# Sheet3.net
KiCad netlist of a schematic drawn in Altium Designer
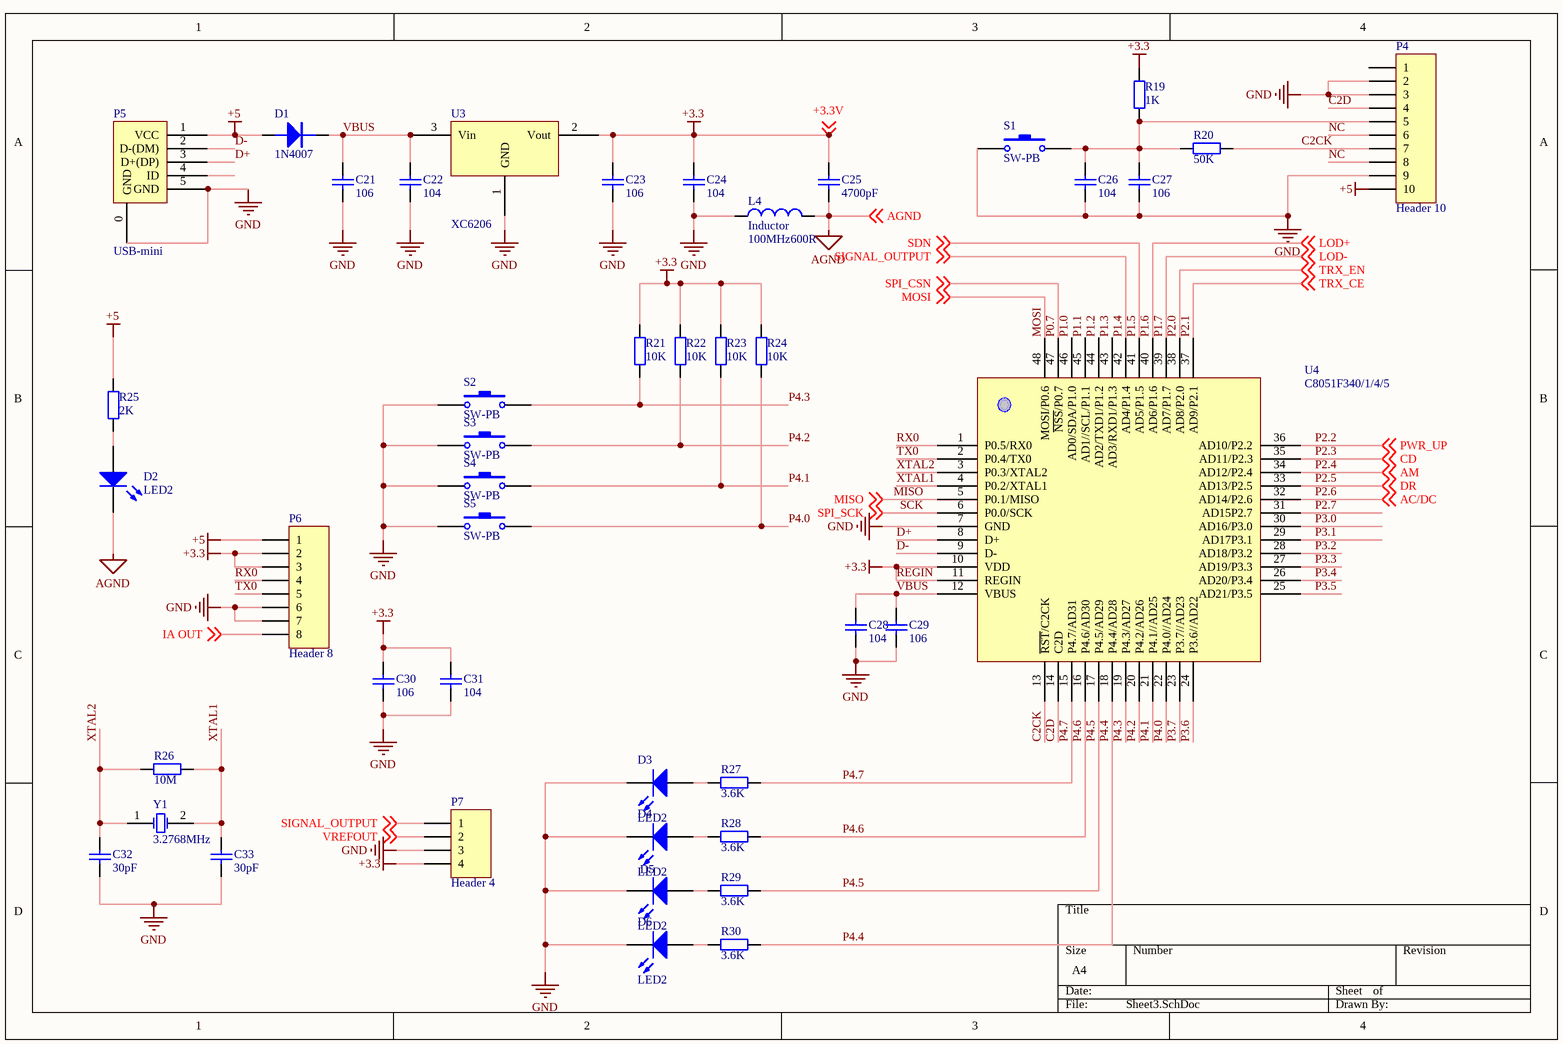
[diagram p0: Sheet3.SchDoc]

(export (version "E")
  (design (tool "Eeschema 10.0.6"))
  (components
    (comp (ref "C21")
      (value "106")
      (footprint "0603C")
      (description "Capacitor")
      (fields (field (name "PUBLISHER") "Altium Limited"))
      (libsource (lib "ECG.SCHLIB") (part "Cap"))
    )
    (comp (ref "C22")
      (value "104")
      (footprint "0603C")
      (description "Capacitor")
      (fields (field (name "PUBLISHER") "Altium Limited"))
      (libsource (lib "ECG.SCHLIB") (part "Cap"))
    )
    (comp (ref "C23")
      (value "106")
      (footprint "0603C")
      (description "Capacitor")
      (fields (field (name "PUBLISHER") "Altium Limited"))
      (libsource (lib "ECG.SCHLIB") (part "Cap"))
    )
    (comp (ref "C24")
      (value "104")
      (footprint "0603C")
      (description "Capacitor")
      (fields (field (name "PUBLISHER") "Altium Limited"))
      (libsource (lib "ECG.SCHLIB") (part "Cap"))
    )
    (comp (ref "C25")
      (value "4700pF")
      (footprint "0603C")
      (description "Capacitor")
      (fields (field (name "PUBLISHER") "Altium Limited"))
      (libsource (lib "ECG.SCHLIB") (part "Cap"))
    )
    (comp (ref "C26")
      (value "104")
      (footprint "0603C")
      (description "Capacitor")
      (fields (field (name "PUBLISHER") "Altium Limited"))
      (libsource (lib "ECG.SCHLIB") (part "Cap"))
    )
    (comp (ref "C27")
      (value "106")
      (footprint "0603C")
      (description "Capacitor")
      (fields (field (name "PUBLISHER") "Altium Limited"))
      (libsource (lib "ECG.SCHLIB") (part "Cap"))
    )
    (comp (ref "C28")
      (value "104")
      (footprint "0603C")
      (description "Capacitor")
      (fields (field (name "PUBLISHER") "Altium Limited"))
      (libsource (lib "ECG.SCHLIB") (part "Cap"))
    )
    (comp (ref "C29")
      (value "106")
      (footprint "0603C")
      (description "Capacitor")
      (fields (field (name "PUBLISHER") "Altium Limited"))
      (libsource (lib "ECG.SCHLIB") (part "Cap"))
    )
    (comp (ref "C30")
      (value "106")
      (footprint "0603C")
      (description "Capacitor")
      (fields (field (name "PUBLISHER") "Altium Limited"))
      (libsource (lib "ECG.SCHLIB") (part "Cap"))
    )
    (comp (ref "C31")
      (value "104")
      (footprint "0603C")
      (description "Capacitor")
      (fields (field (name "PUBLISHER") "Altium Limited"))
      (libsource (lib "ECG.SCHLIB") (part "Cap"))
    )
    (comp (ref "C32")
      (value "30pF")
      (footprint "0603C")
      (description "Capacitor")
      (fields (field (name "PUBLISHER") "Altium Limited"))
      (libsource (lib "ECG.SCHLIB") (part "Cap"))
    )
    (comp (ref "C33")
      (value "30pF")
      (footprint "0603C")
      (description "Capacitor")
      (fields (field (name "PUBLISHER") "Altium Limited"))
      (libsource (lib "ECG.SCHLIB") (part "Cap"))
    )
    (comp (ref "D1") (value "1N4007") (footprint "0603-D") (libsource (lib "ECG2.0") (part "DIODE")))
    (comp (ref "D2")
      (value "LED2")
      (footprint "0603-D")
      (description "Typical RED, GREEN, YELLOW, AMBER GaAs LED")
      (fields (field (name "PUBLISHER") "Altium Limited"))
      (libsource (lib "") (part "LED2_1"))
    )
    (comp (ref "D3")
      (value "LED2")
      (footprint "LED0805R")
      (description "Typical RED, GREEN, YELLOW, AMBER GaAs LED")
      (fields (field (name "PUBLISHER") "Altium Limited"))
      (libsource (lib "Miscellaneous Devices") (part "LED2"))
    )
    (comp (ref "D4")
      (value "LED2")
      (footprint "LED0805R")
      (description "Typical RED, GREEN, YELLOW, AMBER GaAs LED")
      (fields (field (name "PUBLISHER") "Altium Limited"))
      (libsource (lib "Miscellaneous Devices") (part "LED2"))
    )
    (comp (ref "D5")
      (value "LED2")
      (footprint "LED0805R")
      (description "Typical RED, GREEN, YELLOW, AMBER GaAs LED")
      (fields (field (name "PUBLISHER") "Altium Limited"))
      (libsource (lib "Miscellaneous Devices") (part "LED2"))
    )
    (comp (ref "D6")
      (value "LED2")
      (footprint "LED0805R")
      (description "Typical RED, GREEN, YELLOW, AMBER GaAs LED")
      (fields (field (name "PUBLISHER") "Altium Limited"))
      (libsource (lib "Miscellaneous Devices") (part "LED2"))
    )
    (comp (ref "L4")
      (value "Inductor")
      (footprint "0603")
      (fields (field (name "ALTIUM_VALUE") "100MHz600R") (field (name "PUBLISHER") "Altium Limited"))
      (libsource (lib "Miscellaneous Devices") (part "Inductor"))
    )
    (comp (ref "P4")
      (value "Header 10")
      (footprint "IDC10L")
      (description "Header, 10-Pin")
      (fields (field (name "PUBLISHER") "Altium Limited"))
      (libsource (lib "Miscellaneous Connectors") (part "Header 10"))
    )
    (comp (ref "P5") (value "USB-mini") (footprint "USB-Micro") (libsource (lib "ECG2.0") (part "USB-mini")))
    (comp (ref "P6")
      (value "Header 8")
      (footprint "HDR1X8")
      (description "Header, 8-Pin")
      (fields (field (name "PUBLISHER") "Altium Limited"))
      (libsource (lib "Miscellaneous Connectors") (part "Header 8"))
    )
    (comp (ref "P7")
      (value "Header 4")
      (footprint "HDR1X4")
      (description "Header, 4-Pin")
      (fields (field (name "PUBLISHER") "Altium Limited"))
      (libsource (lib "Miscellaneous Connectors") (part "Header 4"))
    )
    (comp (ref "R19")
      (value "1K")
      (footprint "0603R")
      (description "Resistor")
      (fields (field (name "PUBLISHER") "Altium Limited"))
      (libsource (lib "") (part "Res2_2"))
    )
    (comp (ref "R20")
      (value "50K")
      (footprint "0603R")
      (description "Resistor")
      (fields (field (name "PUBLISHER") "Altium Limited"))
      (libsource (lib "") (part "Res2_1"))
    )
    (comp (ref "R21")
      (value "10K")
      (footprint "0603R")
      (description "Resistor")
      (fields (field (name "PUBLISHER") "Altium Limited"))
      (libsource (lib "") (part "Res2_2"))
    )
    (comp (ref "R22")
      (value "10K")
      (footprint "0603R")
      (description "Resistor")
      (fields (field (name "PUBLISHER") "Altium Limited"))
      (libsource (lib "") (part "Res2_2"))
    )
    (comp (ref "R23")
      (value "10K")
      (footprint "0603R")
      (description "Resistor")
      (fields (field (name "PUBLISHER") "Altium Limited"))
      (libsource (lib "") (part "Res2_2"))
    )
    (comp (ref "R24")
      (value "10K")
      (footprint "0603R")
      (description "Resistor")
      (fields (field (name "PUBLISHER") "Altium Limited"))
      (libsource (lib "") (part "Res2_2"))
    )
    (comp (ref "R25")
      (value "2K")
      (footprint "0603R")
      (description "Resistor")
      (fields (field (name "PUBLISHER") "Altium Limited"))
      (libsource (lib "") (part "Res2_2"))
    )
    (comp (ref "R26")
      (value "10M")
      (footprint "0603R")
      (description "Resistor")
      (fields (field (name "PUBLISHER") "Altium Limited"))
      (libsource (lib "ECG.SCHLIB") (part "Res2"))
    )
    (comp (ref "R27")
      (value "3.6K")
      (footprint "0603R")
      (description "Resistor")
      (fields (field (name "PUBLISHER") "Altium Limited"))
      (libsource (lib "ECG.SCHLIB") (part "Res2"))
    )
    (comp (ref "R28")
      (value "3.6K")
      (footprint "0603R")
      (description "Resistor")
      (fields (field (name "PUBLISHER") "Altium Limited"))
      (libsource (lib "ECG.SCHLIB") (part "Res2"))
    )
    (comp (ref "R29")
      (value "3.6K")
      (footprint "0603R")
      (description "Resistor")
      (fields (field (name "PUBLISHER") "Altium Limited"))
      (libsource (lib "ECG.SCHLIB") (part "Res2"))
    )
    (comp (ref "R30")
      (value "3.6K")
      (footprint "0603R")
      (description "Resistor")
      (fields (field (name "PUBLISHER") "Altium Limited"))
      (libsource (lib "ECG.SCHLIB") (part "Res2"))
    )
    (comp (ref "S1")
      (value "SW-PB")
      (footprint "SW-BP-SMD")
      (description "Switch")
      (fields (field (name "PUBLISHER") "Altium Limited"))
      (libsource (lib "Miscellaneous Devices") (part "SW-PB"))
    )
    (comp (ref "S2")
      (value "SW-PB")
      (footprint "SW-BP-SMD")
      (description "Switch")
      (fields (field (name "PUBLISHER") "Altium Limited"))
      (libsource (lib "Miscellaneous Devices") (part "SW-PB"))
    )
    (comp (ref "S3")
      (value "SW-PB")
      (footprint "SW-BP-SMD")
      (description "Switch")
      (fields (field (name "PUBLISHER") "Altium Limited"))
      (libsource (lib "Miscellaneous Devices") (part "SW-PB"))
    )
    (comp (ref "S4")
      (value "SW-PB")
      (footprint "SW-BP-SMD")
      (description "Switch")
      (fields (field (name "PUBLISHER") "Altium Limited"))
      (libsource (lib "Miscellaneous Devices") (part "SW-PB"))
    )
    (comp (ref "S5")
      (value "SW-PB")
      (footprint "SW-BP-SMD")
      (description "Switch")
      (fields (field (name "PUBLISHER") "Altium Limited"))
      (libsource (lib "Miscellaneous Devices") (part "SW-PB"))
    )
    (comp (ref "U3") (value "XC6206") (footprint "SOT-23-123") (libsource (lib "ECG2.0") (part "XC6206")))
    (comp (ref "U4")
      (value "C8051F340/1/4/5")
      (footprint "TQFP48_M")
      (libsource (lib "ECG2.0") (part "C8051F340/1/4/5"))
    )
    (comp (ref "Y1")
      (value "3.2768MHz")
      (footprint "CY2")
      (description "Crystal Oscillator")
      (fields (field (name "PUBLISHER") "Altium Limited"))
      (libsource (lib "Miscellaneous Devices") (part "XTAL"))
    )
  )
  (nets
    (net (code "1") (name "+3.3") (class "Default")
      (node (ref "C23") (pin "2") (pinfunction "2_2") (pintype "passive"))
      (node (ref "C24") (pin "2") (pinfunction "2_2") (pintype "passive"))
      (node (ref "C25") (pin "2") (pinfunction "2_2") (pintype "passive"))
      (node (ref "C30") (pin "2") (pinfunction "2_2") (pintype "passive"))
      (node (ref "C31") (pin "2") (pinfunction "2_2") (pintype "passive"))
      (node (ref "P6") (pin "2") (pinfunction "2_2") (pintype "passive"))
      (node (ref "P6") (pin "3") (pinfunction "3_3") (pintype "passive"))
      (node (ref "P7") (pin "4") (pinfunction "4_4") (pintype "passive"))
      (node (ref "R19") (pin "2") (pinfunction "2_2") (pintype "passive"))
      (node (ref "R21") (pin "2") (pinfunction "2_2") (pintype "passive"))
      (node (ref "R22") (pin "2") (pinfunction "2_2") (pintype "passive"))
      (node (ref "R23") (pin "2") (pinfunction "2_2") (pintype "passive"))
      (node (ref "R24") (pin "2") (pinfunction "2_2") (pintype "passive"))
      (node (ref "U3") (pin "2") (pinfunction "Vout_2") (pintype "passive"))
      (node (ref "U4") (pin "10") (pinfunction "VDD_10") (pintype "passive"))
      (node (ref "U4") (pin "11") (pinfunction "REGIN_11") (pintype "passive"))
    )
    (net (code "2") (name "+5") (class "Default")
      (node (ref "D1") (pin "A") (pintype "passive"))
      (node (ref "P4") (pin "10") (pinfunction "10_10") (pintype "passive"))
      (node (ref "P5") (pin "1") (pinfunction "VCC_1") (pintype "passive"))
      (node (ref "P6") (pin "1") (pinfunction "1_1") (pintype "passive"))
      (node (ref "R25") (pin "2") (pinfunction "2_2") (pintype "passive"))
    )
    (net (code "3") (name "/C2CK") (class "Default")
      (node (ref "P4") (pin "7") (pinfunction "7_7") (pintype "passive"))
      (node (ref "R20") (pin "1") (pinfunction "1_1") (pintype "passive"))
      (node (ref "U4") (pin "13") (pinfunction "~{RST}/C2CK_13") (pintype "passive"))
    )
    (net (code "4") (name "/C2D") (class "Default")
      (node (ref "P4") (pin "4") (pinfunction "4_4") (pintype "passive"))
      (node (ref "U4") (pin "14") (pinfunction "C2D_14") (pintype "passive"))
    )
    (net (code "5") (name "/D+") (class "Default")
      (node (ref "P5") (pin "3") (pinfunction "D+(DP)_3") (pintype "passive"))
      (node (ref "U4") (pin "8") (pinfunction "D+_8") (pintype "passive"))
    )
    (net (code "6") (name "/D-") (class "Default")
      (node (ref "P5") (pin "2") (pinfunction "D-(DM)_2") (pintype "passive"))
      (node (ref "U4") (pin "9") (pinfunction "D-_9") (pintype "passive"))
    )
    (net (code "7") (name "/NC") (class "Default")
      (node (ref "P4") (pin "6") (pinfunction "6_6") (pintype "passive"))
      (node (ref "P4") (pin "8") (pinfunction "8_8") (pintype "passive"))
    )
    (net (code "8") (name "/P1.0") (class "Default")
      (node (ref "U4") (pin "46") (pinfunction "AD0/SDA/P1.0_46") (pintype "passive"))
    )
    (net (code "9") (name "/P1.1") (class "Default")
      (node (ref "U4") (pin "45") (pinfunction "AD1//SCL/P1.1_45") (pintype "passive"))
    )
    (net (code "10") (name "/P1.2") (class "Default")
      (node (ref "U4") (pin "44") (pinfunction "AD2/TXD1/P1.2_44") (pintype "passive"))
    )
    (net (code "11") (name "/P1.3") (class "Default")
      (node (ref "U4") (pin "43") (pinfunction "AD3/RXD1/P1.3_43") (pintype "passive"))
    )
    (net (code "12") (name "/P2.7") (class "Default")
      (node (ref "U4") (pin "31") (pinfunction "AD15P2.7_31") (pintype "passive"))
    )
    (net (code "13") (name "/P3.0") (class "Default")
      (node (ref "U4") (pin "30") (pinfunction "AD16/P3.0_30") (pintype "passive"))
    )
    (net (code "14") (name "/P3.1") (class "Default")
      (node (ref "U4") (pin "29") (pinfunction "AD17P3.1_29") (pintype "passive"))
    )
    (net (code "15") (name "/P3.2") (class "Default")
      (node (ref "U4") (pin "28") (pinfunction "AD18/P3.2_28") (pintype "passive"))
    )
    (net (code "16") (name "/P3.3") (class "Default")
      (node (ref "U4") (pin "27") (pinfunction "AD19/P3.3_27") (pintype "passive"))
    )
    (net (code "17") (name "/P3.4") (class "Default")
      (node (ref "U4") (pin "26") (pinfunction "AD20/P3.4_26") (pintype "passive"))
    )
    (net (code "18") (name "/P3.5") (class "Default")
      (node (ref "U4") (pin "25") (pinfunction "AD21/P3.5_25") (pintype "passive"))
    )
    (net (code "19") (name "/P3.6") (class "Default")
      (node (ref "U4") (pin "24") (pinfunction "P3.6//AD22_24") (pintype "passive"))
    )
    (net (code "20") (name "/P3.7") (class "Default")
      (node (ref "U4") (pin "23") (pinfunction "P3.7//AD23_23") (pintype "passive"))
    )
    (net (code "21") (name "/P4.0") (class "Default")
      (node (ref "R24") (pin "1") (pinfunction "1_1") (pintype "passive"))
      (node (ref "S5") (pin "2") (pinfunction "2_2") (pintype "passive"))
      (node (ref "U4") (pin "22") (pinfunction "P4.0//AD24_22") (pintype "passive"))
    )
    (net (code "22") (name "/P4.1") (class "Default")
      (node (ref "R23") (pin "1") (pinfunction "1_1") (pintype "passive"))
      (node (ref "S4") (pin "2") (pinfunction "2_2") (pintype "passive"))
      (node (ref "U4") (pin "21") (pinfunction "P4.1//AD25_21") (pintype "passive"))
    )
    (net (code "23") (name "/P4.2") (class "Default")
      (node (ref "R22") (pin "1") (pinfunction "1_1") (pintype "passive"))
      (node (ref "S3") (pin "2") (pinfunction "2_2") (pintype "passive"))
      (node (ref "U4") (pin "20") (pinfunction "P4.2/AD26_20") (pintype "passive"))
    )
    (net (code "24") (name "/P4.3") (class "Default")
      (node (ref "R21") (pin "1") (pinfunction "1_1") (pintype "passive"))
      (node (ref "S2") (pin "2") (pinfunction "2_2") (pintype "passive"))
      (node (ref "U4") (pin "19") (pinfunction "P4.3/AD27_19") (pintype "passive"))
    )
    (net (code "25") (name "/P4.4") (class "Default")
      (node (ref "R30") (pin "2") (pinfunction "2_2") (pintype "passive"))
      (node (ref "U4") (pin "18") (pinfunction "P4.4/AD28_18") (pintype "passive"))
    )
    (net (code "26") (name "/P4.5") (class "Default")
      (node (ref "R29") (pin "2") (pinfunction "2_2") (pintype "passive"))
      (node (ref "U4") (pin "17") (pinfunction "P4.5/AD29_17") (pintype "passive"))
    )
    (net (code "27") (name "/P4.6") (class "Default")
      (node (ref "R28") (pin "2") (pinfunction "2_2") (pintype "passive"))
      (node (ref "U4") (pin "16") (pinfunction "P4.6/AD30_16") (pintype "passive"))
    )
    (net (code "28") (name "/P4.7") (class "Default")
      (node (ref "R27") (pin "2") (pinfunction "2_2") (pintype "passive"))
      (node (ref "U4") (pin "15") (pinfunction "P4.7/AD31_15") (pintype "passive"))
    )
    (net (code "29") (name "/RX0") (class "Default")
      (node (ref "P6") (pin "4") (pinfunction "4_4") (pintype "passive"))
      (node (ref "U4") (pin "1") (pinfunction "P0.5/RX0_1") (pintype "passive"))
    )
    (net (code "30") (name "/TX0") (class "Default")
      (node (ref "P6") (pin "5") (pinfunction "5_5") (pintype "passive"))
      (node (ref "U4") (pin "2") (pinfunction "P0.4/TX0_2") (pintype "passive"))
    )
    (net (code "31") (name "/VBUS") (class "Default")
      (node (ref "C21") (pin "2") (pinfunction "2_2") (pintype "passive"))
      (node (ref "C22") (pin "2") (pinfunction "2_2") (pintype "passive"))
      (node (ref "C28") (pin "2") (pinfunction "2_2") (pintype "passive"))
      (node (ref "C29") (pin "2") (pinfunction "2_2") (pintype "passive"))
      (node (ref "D1") (pin "K") (pintype "passive"))
      (node (ref "U3") (pin "3") (pinfunction "Vin_3") (pintype "passive"))
      (node (ref "U4") (pin "12") (pinfunction "VBUS_12") (pintype "passive"))
    )
    (net (code "32") (name "/XTAL1") (class "Default")
      (node (ref "C33") (pin "2") (pinfunction "2_2") (pintype "passive"))
      (node (ref "R26") (pin "2") (pinfunction "2_2") (pintype "passive"))
      (node (ref "U4") (pin "4") (pinfunction "P0.2/XTAL1_4") (pintype "passive"))
      (node (ref "Y1") (pin "2") (pinfunction "OSC2_2") (pintype "passive"))
    )
    (net (code "33") (name "/XTAL2") (class "Default")
      (node (ref "C32") (pin "2") (pinfunction "2_2") (pintype "passive"))
      (node (ref "R26") (pin "1") (pinfunction "1_1") (pintype "passive"))
      (node (ref "U4") (pin "3") (pinfunction "P0.3/XTAL2_3") (pintype "passive"))
      (node (ref "Y1") (pin "1") (pinfunction "OSC1_1") (pintype "passive"))
    )
    (net (code "34") (name "AC{slash}DC") (class "Default")
      (node (ref "U4") (pin "32") (pinfunction "AD14/P2.6_32") (pintype "passive"))
    )
    (net (code "35") (name "AGND") (class "Default")
      (node (ref "C25") (pin "1") (pinfunction "1_1") (pintype "passive"))
      (node (ref "D2") (pin "K") (pinfunction "2_K") (pintype "passive"))
      (node (ref "L4") (pin "2") (pinfunction "2_2") (pintype "passive"))
    )
    (net (code "36") (name "AM") (class "Default")
      (node (ref "U4") (pin "34") (pinfunction "AD12/P2.4_34") (pintype "passive"))
    )
    (net (code "37") (name "CD") (class "Default")
      (node (ref "U4") (pin "35") (pinfunction "AD11/P2.3_35") (pintype "passive"))
    )
    (net (code "38") (name "DR") (class "Default")
      (node (ref "U4") (pin "33") (pinfunction "AD13/P2.5_33") (pintype "passive"))
    )
    (net (code "39") (name "GND") (class "Default")
      (node (ref "C21") (pin "1") (pinfunction "1_1") (pintype "passive"))
      (node (ref "C22") (pin "1") (pinfunction "1_1") (pintype "passive"))
      (node (ref "C23") (pin "1") (pinfunction "1_1") (pintype "passive"))
      (node (ref "C24") (pin "1") (pinfunction "1_1") (pintype "passive"))
      (node (ref "C26") (pin "1") (pinfunction "1_1") (pintype "passive"))
      (node (ref "C27") (pin "1") (pinfunction "1_1") (pintype "passive"))
      (node (ref "C28") (pin "1") (pinfunction "1_1") (pintype "passive"))
      (node (ref "C29") (pin "1") (pinfunction "1_1") (pintype "passive"))
      (node (ref "C30") (pin "1") (pinfunction "1_1") (pintype "passive"))
      (node (ref "C31") (pin "1") (pinfunction "1_1") (pintype "passive"))
      (node (ref "C32") (pin "1") (pinfunction "1_1") (pintype "passive"))
      (node (ref "C33") (pin "1") (pinfunction "1_1") (pintype "passive"))
      (node (ref "D3") (pin "2") (pinfunction "2_2") (pintype "passive"))
      (node (ref "D4") (pin "2") (pinfunction "2_2") (pintype "passive"))
      (node (ref "D5") (pin "2") (pinfunction "2_2") (pintype "passive"))
      (node (ref "D6") (pin "2") (pinfunction "2_2") (pintype "passive"))
      (node (ref "L4") (pin "1") (pinfunction "1_1") (pintype "passive"))
      (node (ref "P4") (pin "2") (pinfunction "2_2") (pintype "passive"))
      (node (ref "P4") (pin "3") (pinfunction "3_3") (pintype "passive"))
      (node (ref "P4") (pin "9") (pinfunction "9_9") (pintype "passive"))
      (node (ref "P5") (pin "0") (pinfunction "GND_0") (pintype "passive"))
      (node (ref "P5") (pin "5") (pinfunction "GND_5") (pintype "passive"))
      (node (ref "P6") (pin "6") (pinfunction "6_6") (pintype "passive"))
      (node (ref "P6") (pin "7") (pinfunction "7_7") (pintype "passive"))
      (node (ref "P7") (pin "3") (pinfunction "3_3") (pintype "passive"))
      (node (ref "S1") (pin "1") (pinfunction "1_1") (pintype "passive"))
      (node (ref "S2") (pin "1") (pinfunction "1_1") (pintype "passive"))
      (node (ref "S3") (pin "1") (pinfunction "1_1") (pintype "passive"))
      (node (ref "S4") (pin "1") (pinfunction "1_1") (pintype "passive"))
      (node (ref "S5") (pin "1") (pinfunction "1_1") (pintype "passive"))
      (node (ref "U3") (pin "1") (pinfunction "GND_1") (pintype "passive"))
      (node (ref "U4") (pin "7") (pinfunction "GND_7") (pintype "passive"))
    )
    (net (code "40") (name "IA OUT") (class "Default")
      (node (ref "P6") (pin "8") (pinfunction "8_8") (pintype "passive"))
    )
    (net (code "41") (name "LOD+") (class "Default")
      (node (ref "U4") (pin "40") (pinfunction "AD6/P1.6_40") (pintype "passive"))
    )
    (net (code "42") (name "LOD-") (class "Default")
      (node (ref "U4") (pin "39") (pinfunction "AD7/P1.7_39") (pintype "passive"))
    )
    (net (code "43") (name "MISO") (class "Default")
      (node (ref "U4") (pin "5") (pinfunction "P0.1/MISO_5") (pintype "passive"))
    )
    (net (code "44") (name "MOSI") (class "Default")
      (node (ref "U4") (pin "48") (pinfunction "MOSI/P0.6_48") (pintype "passive"))
    )
    (net (code "45") (name "Net-(C26-Pad2)") (class "Default")
      (node (ref "C26") (pin "2") (pinfunction "2_2") (pintype "passive"))
      (node (ref "C27") (pin "2") (pinfunction "2_2") (pintype "passive"))
      (node (ref "P4") (pin "5") (pinfunction "5_5") (pintype "passive"))
      (node (ref "R19") (pin "1") (pinfunction "1_1") (pintype "passive"))
      (node (ref "R20") (pin "2") (pinfunction "2_2") (pintype "passive"))
      (node (ref "S1") (pin "2") (pinfunction "2_2") (pintype "passive"))
    )
    (net (code "46") (name "Net-(D2-1)") (class "Default")
      (node (ref "D2") (pin "A") (pinfunction "1_A") (pintype "passive"))
      (node (ref "R25") (pin "1") (pinfunction "1_1") (pintype "passive"))
    )
    (net (code "47") (name "Net-(D3-Pad1)") (class "Default")
      (node (ref "D3") (pin "1") (pinfunction "1_1") (pintype "passive"))
      (node (ref "R27") (pin "1") (pinfunction "1_1") (pintype "passive"))
    )
    (net (code "48") (name "Net-(D4-Pad1)") (class "Default")
      (node (ref "D4") (pin "1") (pinfunction "1_1") (pintype "passive"))
      (node (ref "R28") (pin "1") (pinfunction "1_1") (pintype "passive"))
    )
    (net (code "49") (name "Net-(D5-Pad1)") (class "Default")
      (node (ref "D5") (pin "1") (pinfunction "1_1") (pintype "passive"))
      (node (ref "R29") (pin "1") (pinfunction "1_1") (pintype "passive"))
    )
    (net (code "50") (name "Net-(D6-Pad1)") (class "Default")
      (node (ref "D6") (pin "1") (pinfunction "1_1") (pintype "passive"))
      (node (ref "R30") (pin "1") (pinfunction "1_1") (pintype "passive"))
    )
    (net (code "51") (name "PWR_UP") (class "Default")
      (node (ref "U4") (pin "36") (pinfunction "AD10/P2.2_36") (pintype "passive"))
    )
    (net (code "52") (name "SDN") (class "Default")
      (node (ref "U4") (pin "41") (pinfunction "AD5/P1.5_41") (pintype "passive"))
    )
    (net (code "53") (name "SIGNAL_OUTPUT") (class "Default")
      (node (ref "P7") (pin "1") (pinfunction "1_1") (pintype "passive"))
      (node (ref "U4") (pin "42") (pinfunction "AD4/P1.4_42") (pintype "passive"))
    )
    (net (code "54") (name "SPI_CSN") (class "Default")
      (node (ref "U4") (pin "47") (pinfunction "~{NSS}/P0.7_47") (pintype "passive"))
    )
    (net (code "55") (name "SPI_SCK") (class "Default")
      (node (ref "U4") (pin "6") (pinfunction "P0.0/SCK_6") (pintype "passive"))
    )
    (net (code "56") (name "TRX_CE") (class "Default")
      (node (ref "U4") (pin "37") (pinfunction "AD9/P2.1_37") (pintype "passive"))
    )
    (net (code "57") (name "TRX_EN") (class "Default")
      (node (ref "U4") (pin "38") (pinfunction "AD8/P2.0_38") (pintype "passive"))
    )
    (net (code "58") (name "VREFOUT") (class "Default")
      (node (ref "P7") (pin "2") (pinfunction "2_2") (pintype "passive"))
    )
    (net (code "59") (name "unconnected-(P4-Pad1)") (class "Default")
      (node (ref "P4") (pin "1") (pinfunction "1_1") (pintype "passive"))
    )
    (net (code "60") (name "unconnected-(P5-ID-Pad4)") (class "Default")
      (node (ref "P5") (pin "4") (pinfunction "ID_4") (pintype "passive"))
    )
  )
)
